# SparkFun_LED_Array_8x7.net
KiCad netlist of a schematic drawn in EAGLE
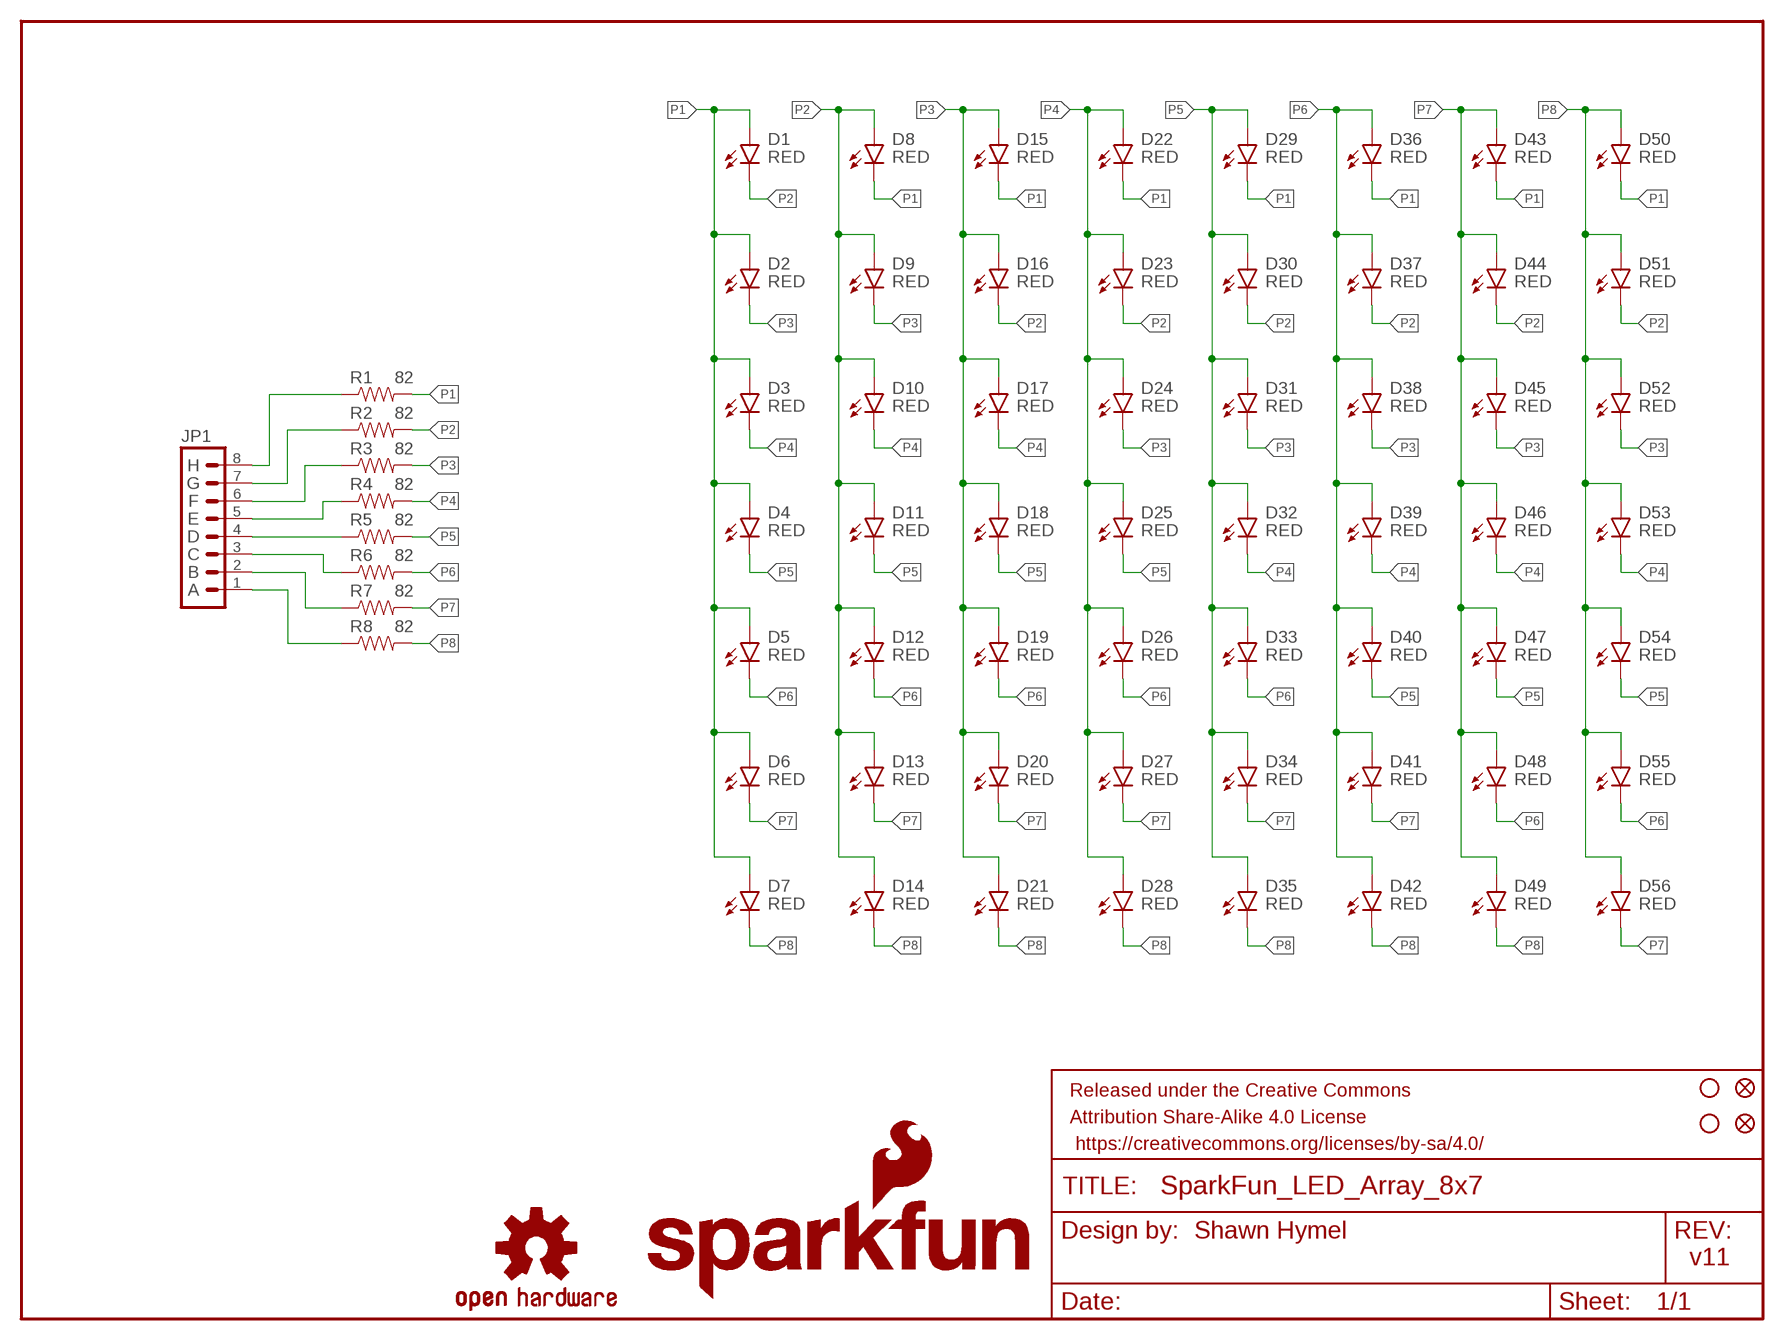
[diagram p0: schematic, sheet 1]

(export (version "E")
  (design (tool "Eeschema 10.0.6"))
  (components
    (comp (ref "D1")
      (value "RED")
      (footprint "eagle-import:LED-0603")
      (libsource (lib "eagle-import") (part "LED-RED0603"))
    )
    (comp (ref "D2")
      (value "RED")
      (footprint "eagle-import:LED-0603")
      (libsource (lib "eagle-import") (part "LED-RED0603"))
    )
    (comp (ref "D3")
      (value "RED")
      (footprint "eagle-import:LED-0603")
      (libsource (lib "eagle-import") (part "LED-RED0603"))
    )
    (comp (ref "D4")
      (value "RED")
      (footprint "eagle-import:LED-0603")
      (libsource (lib "eagle-import") (part "LED-RED0603"))
    )
    (comp (ref "D5")
      (value "RED")
      (footprint "eagle-import:LED-0603")
      (libsource (lib "eagle-import") (part "LED-RED0603"))
    )
    (comp (ref "D6")
      (value "RED")
      (footprint "eagle-import:LED-0603")
      (libsource (lib "eagle-import") (part "LED-RED0603"))
    )
    (comp (ref "D7")
      (value "RED")
      (footprint "eagle-import:LED-0603")
      (libsource (lib "eagle-import") (part "LED-RED0603"))
    )
    (comp (ref "D8")
      (value "RED")
      (footprint "eagle-import:LED-0603")
      (libsource (lib "eagle-import") (part "LED-RED0603"))
    )
    (comp (ref "D9")
      (value "RED")
      (footprint "eagle-import:LED-0603")
      (libsource (lib "eagle-import") (part "LED-RED0603"))
    )
    (comp (ref "D10")
      (value "RED")
      (footprint "eagle-import:LED-0603")
      (libsource (lib "eagle-import") (part "LED-RED0603"))
    )
    (comp (ref "D11")
      (value "RED")
      (footprint "eagle-import:LED-0603")
      (libsource (lib "eagle-import") (part "LED-RED0603"))
    )
    (comp (ref "D12")
      (value "RED")
      (footprint "eagle-import:LED-0603")
      (libsource (lib "eagle-import") (part "LED-RED0603"))
    )
    (comp (ref "D13")
      (value "RED")
      (footprint "eagle-import:LED-0603")
      (libsource (lib "eagle-import") (part "LED-RED0603"))
    )
    (comp (ref "D14")
      (value "RED")
      (footprint "eagle-import:LED-0603")
      (libsource (lib "eagle-import") (part "LED-RED0603"))
    )
    (comp (ref "D15")
      (value "RED")
      (footprint "eagle-import:LED-0603")
      (libsource (lib "eagle-import") (part "LED-RED0603"))
    )
    (comp (ref "D16")
      (value "RED")
      (footprint "eagle-import:LED-0603")
      (libsource (lib "eagle-import") (part "LED-RED0603"))
    )
    (comp (ref "D17")
      (value "RED")
      (footprint "eagle-import:LED-0603")
      (libsource (lib "eagle-import") (part "LED-RED0603"))
    )
    (comp (ref "D18")
      (value "RED")
      (footprint "eagle-import:LED-0603")
      (libsource (lib "eagle-import") (part "LED-RED0603"))
    )
    (comp (ref "D19")
      (value "RED")
      (footprint "eagle-import:LED-0603")
      (libsource (lib "eagle-import") (part "LED-RED0603"))
    )
    (comp (ref "D20")
      (value "RED")
      (footprint "eagle-import:LED-0603")
      (libsource (lib "eagle-import") (part "LED-RED0603"))
    )
    (comp (ref "D21")
      (value "RED")
      (footprint "eagle-import:LED-0603")
      (libsource (lib "eagle-import") (part "LED-RED0603"))
    )
    (comp (ref "D22")
      (value "RED")
      (footprint "eagle-import:LED-0603")
      (libsource (lib "eagle-import") (part "LED-RED0603"))
    )
    (comp (ref "D23")
      (value "RED")
      (footprint "eagle-import:LED-0603")
      (libsource (lib "eagle-import") (part "LED-RED0603"))
    )
    (comp (ref "D24")
      (value "RED")
      (footprint "eagle-import:LED-0603")
      (libsource (lib "eagle-import") (part "LED-RED0603"))
    )
    (comp (ref "D25")
      (value "RED")
      (footprint "eagle-import:LED-0603")
      (libsource (lib "eagle-import") (part "LED-RED0603"))
    )
    (comp (ref "D26")
      (value "RED")
      (footprint "eagle-import:LED-0603")
      (libsource (lib "eagle-import") (part "LED-RED0603"))
    )
    (comp (ref "D27")
      (value "RED")
      (footprint "eagle-import:LED-0603")
      (libsource (lib "eagle-import") (part "LED-RED0603"))
    )
    (comp (ref "D28")
      (value "RED")
      (footprint "eagle-import:LED-0603")
      (libsource (lib "eagle-import") (part "LED-RED0603"))
    )
    (comp (ref "D29")
      (value "RED")
      (footprint "eagle-import:LED-0603")
      (libsource (lib "eagle-import") (part "LED-RED0603"))
    )
    (comp (ref "D30")
      (value "RED")
      (footprint "eagle-import:LED-0603")
      (libsource (lib "eagle-import") (part "LED-RED0603"))
    )
    (comp (ref "D31")
      (value "RED")
      (footprint "eagle-import:LED-0603")
      (libsource (lib "eagle-import") (part "LED-RED0603"))
    )
    (comp (ref "D32")
      (value "RED")
      (footprint "eagle-import:LED-0603")
      (libsource (lib "eagle-import") (part "LED-RED0603"))
    )
    (comp (ref "D33")
      (value "RED")
      (footprint "eagle-import:LED-0603")
      (libsource (lib "eagle-import") (part "LED-RED0603"))
    )
    (comp (ref "D34")
      (value "RED")
      (footprint "eagle-import:LED-0603")
      (libsource (lib "eagle-import") (part "LED-RED0603"))
    )
    (comp (ref "D35")
      (value "RED")
      (footprint "eagle-import:LED-0603")
      (libsource (lib "eagle-import") (part "LED-RED0603"))
    )
    (comp (ref "D36")
      (value "RED")
      (footprint "eagle-import:LED-0603")
      (libsource (lib "eagle-import") (part "LED-RED0603"))
    )
    (comp (ref "D37")
      (value "RED")
      (footprint "eagle-import:LED-0603")
      (libsource (lib "eagle-import") (part "LED-RED0603"))
    )
    (comp (ref "D38")
      (value "RED")
      (footprint "eagle-import:LED-0603")
      (libsource (lib "eagle-import") (part "LED-RED0603"))
    )
    (comp (ref "D39")
      (value "RED")
      (footprint "eagle-import:LED-0603")
      (libsource (lib "eagle-import") (part "LED-RED0603"))
    )
    (comp (ref "D40")
      (value "RED")
      (footprint "eagle-import:LED-0603")
      (libsource (lib "eagle-import") (part "LED-RED0603"))
    )
    (comp (ref "D41")
      (value "RED")
      (footprint "eagle-import:LED-0603")
      (libsource (lib "eagle-import") (part "LED-RED0603"))
    )
    (comp (ref "D42")
      (value "RED")
      (footprint "eagle-import:LED-0603")
      (libsource (lib "eagle-import") (part "LED-RED0603"))
    )
    (comp (ref "D43")
      (value "RED")
      (footprint "eagle-import:LED-0603")
      (libsource (lib "eagle-import") (part "LED-RED0603"))
    )
    (comp (ref "D44")
      (value "RED")
      (footprint "eagle-import:LED-0603")
      (libsource (lib "eagle-import") (part "LED-RED0603"))
    )
    (comp (ref "D45")
      (value "RED")
      (footprint "eagle-import:LED-0603")
      (libsource (lib "eagle-import") (part "LED-RED0603"))
    )
    (comp (ref "D46")
      (value "RED")
      (footprint "eagle-import:LED-0603")
      (libsource (lib "eagle-import") (part "LED-RED0603"))
    )
    (comp (ref "D47")
      (value "RED")
      (footprint "eagle-import:LED-0603")
      (libsource (lib "eagle-import") (part "LED-RED0603"))
    )
    (comp (ref "D48")
      (value "RED")
      (footprint "eagle-import:LED-0603")
      (libsource (lib "eagle-import") (part "LED-RED0603"))
    )
    (comp (ref "D49")
      (value "RED")
      (footprint "eagle-import:LED-0603")
      (libsource (lib "eagle-import") (part "LED-RED0603"))
    )
    (comp (ref "D50")
      (value "RED")
      (footprint "eagle-import:LED-0603")
      (libsource (lib "eagle-import") (part "LED-RED0603"))
    )
    (comp (ref "D51")
      (value "RED")
      (footprint "eagle-import:LED-0603")
      (libsource (lib "eagle-import") (part "LED-RED0603"))
    )
    (comp (ref "D52")
      (value "RED")
      (footprint "eagle-import:LED-0603")
      (libsource (lib "eagle-import") (part "LED-RED0603"))
    )
    (comp (ref "D53")
      (value "RED")
      (footprint "eagle-import:LED-0603")
      (libsource (lib "eagle-import") (part "LED-RED0603"))
    )
    (comp (ref "D54")
      (value "RED")
      (footprint "eagle-import:LED-0603")
      (libsource (lib "eagle-import") (part "LED-RED0603"))
    )
    (comp (ref "D55")
      (value "RED")
      (footprint "eagle-import:LED-0603")
      (libsource (lib "eagle-import") (part "LED-RED0603"))
    )
    (comp (ref "D56")
      (value "RED")
      (footprint "eagle-import:LED-0603")
      (libsource (lib "eagle-import") (part "LED-RED0603"))
    )
    (comp (ref "FID1")
      (value "FIDUCIAL1X2")
      (footprint "eagle-import:FIDUCIAL-1X2")
      (libsource (lib "eagle-import") (part "FIDUCIAL1X2"))
    )
    (comp (ref "FID2")
      (value "FIDUCIAL1X2")
      (footprint "eagle-import:FIDUCIAL-1X2")
      (libsource (lib "eagle-import") (part "FIDUCIAL1X2"))
    )
    (comp (ref "FRAME1")
      (value "FRAME-LETTER")
      (footprint "eagle-import:CREATIVE_COMMONS")
      (libsource (lib "eagle-import") (part "FRAME-LETTER"))
    )
    (comp (ref "JP1")
      (value "M08LOCK_NO_SILK")
      (footprint "eagle-import:1X08_LOCK_NO_SILK")
      (libsource (lib "eagle-import") (part "M08LOCK_NO_SILK"))
    )
    (comp (ref "LOGO2")
      (value "OSHW-LOGOS")
      (footprint "eagle-import:OSHW-LOGO-S")
      (libsource (lib "eagle-import") (part "OSHW-LOGOS"))
    )
    (comp (ref "R1")
      (value "82")
      (footprint "eagle-import:0603-RES")
      (libsource (lib "eagle-import") (part "82OHM-1/10W-1%(0603)SMD"))
    )
    (comp (ref "R2")
      (value "82")
      (footprint "eagle-import:0603-RES")
      (libsource (lib "eagle-import") (part "82OHM-1/10W-1%(0603)SMD"))
    )
    (comp (ref "R3")
      (value "82")
      (footprint "eagle-import:0603-RES")
      (libsource (lib "eagle-import") (part "82OHM-1/10W-1%(0603)SMD"))
    )
    (comp (ref "R4")
      (value "82")
      (footprint "eagle-import:0603-RES")
      (libsource (lib "eagle-import") (part "82OHM-1/10W-1%(0603)SMD"))
    )
    (comp (ref "R5")
      (value "82")
      (footprint "eagle-import:0603-RES")
      (libsource (lib "eagle-import") (part "82OHM-1/10W-1%(0603)SMD"))
    )
    (comp (ref "R6")
      (value "82")
      (footprint "eagle-import:0603-RES")
      (libsource (lib "eagle-import") (part "82OHM-1/10W-1%(0603)SMD"))
    )
    (comp (ref "R7")
      (value "82")
      (footprint "eagle-import:0603-RES")
      (libsource (lib "eagle-import") (part "82OHM-1/10W-1%(0603)SMD"))
    )
    (comp (ref "R8")
      (value "82")
      (footprint "eagle-import:0603-RES")
      (libsource (lib "eagle-import") (part "82OHM-1/10W-1%(0603)SMD"))
    )
    (comp (ref "STANDOFF1")
      (value "STAND-OFF")
      (footprint "eagle-import:STAND-OFF")
      (libsource (lib "eagle-import") (part "STAND-OFF"))
    )
    (comp (ref "STANDOFF2")
      (value "STAND-OFF")
      (footprint "eagle-import:STAND-OFF")
      (libsource (lib "eagle-import") (part "STAND-OFF"))
    )
    (comp (ref "U$1")
      (value "SFE_LOGO_NAME_FLAME.1_INCH")
      (footprint "eagle-import:SFE_LOGO_NAME_FLAME_.1")
      (libsource (lib "eagle-import") (part "SFE_LOGO_NAME_FLAME.1_INCH"))
    )
  )
  (nets
    (net (code "1") (name "Net-(JP1-Pad1)") (class "Default")
      (node (ref "JP1") (pin "1") (pinfunction "1_1") (pintype "passive"))
      (node (ref "R8") (pin "1") (pinfunction "1_1") (pintype "passive"))
    )
    (net (code "2") (name "Net-(JP1-Pad2)") (class "Default")
      (node (ref "JP1") (pin "2") (pinfunction "2_2") (pintype "passive"))
      (node (ref "R7") (pin "1") (pinfunction "1_1") (pintype "passive"))
    )
    (net (code "3") (name "Net-(JP1-Pad3)") (class "Default")
      (node (ref "JP1") (pin "3") (pinfunction "3_3") (pintype "passive"))
      (node (ref "R6") (pin "1") (pinfunction "1_1") (pintype "passive"))
    )
    (net (code "4") (name "Net-(JP1-Pad4)") (class "Default")
      (node (ref "JP1") (pin "4") (pinfunction "4_4") (pintype "passive"))
      (node (ref "R5") (pin "1") (pinfunction "1_1") (pintype "passive"))
    )
    (net (code "5") (name "Net-(JP1-Pad5)") (class "Default")
      (node (ref "JP1") (pin "5") (pinfunction "5_5") (pintype "passive"))
      (node (ref "R4") (pin "1") (pinfunction "1_1") (pintype "passive"))
    )
    (net (code "6") (name "Net-(JP1-Pad6)") (class "Default")
      (node (ref "JP1") (pin "6") (pinfunction "6_6") (pintype "passive"))
      (node (ref "R3") (pin "1") (pinfunction "1_1") (pintype "passive"))
    )
    (net (code "7") (name "Net-(JP1-Pad7)") (class "Default")
      (node (ref "JP1") (pin "7") (pinfunction "7_7") (pintype "passive"))
      (node (ref "R2") (pin "1") (pinfunction "1_1") (pintype "passive"))
    )
    (net (code "8") (name "Net-(JP1-Pad8)") (class "Default")
      (node (ref "JP1") (pin "8") (pinfunction "8_8") (pintype "passive"))
      (node (ref "R1") (pin "1") (pinfunction "1_1") (pintype "passive"))
    )
    (net (code "9") (name "P1") (class "Default")
      (node (ref "D1") (pin "A") (pinfunction "A_A") (pintype "passive"))
      (node (ref "D15") (pin "C") (pinfunction "C_C") (pintype "passive"))
      (node (ref "D2") (pin "A") (pinfunction "A_A") (pintype "passive"))
      (node (ref "D22") (pin "C") (pinfunction "C_C") (pintype "passive"))
      (node (ref "D29") (pin "C") (pinfunction "C_C") (pintype "passive"))
      (node (ref "D3") (pin "A") (pinfunction "A_A") (pintype "passive"))
      (node (ref "D36") (pin "C") (pinfunction "C_C") (pintype "passive"))
      (node (ref "D4") (pin "A") (pinfunction "A_A") (pintype "passive"))
      (node (ref "D43") (pin "C") (pinfunction "C_C") (pintype "passive"))
      (node (ref "D5") (pin "A") (pinfunction "A_A") (pintype "passive"))
      (node (ref "D50") (pin "C") (pinfunction "C_C") (pintype "passive"))
      (node (ref "D6") (pin "A") (pinfunction "A_A") (pintype "passive"))
      (node (ref "D7") (pin "A") (pinfunction "A_A") (pintype "passive"))
      (node (ref "D8") (pin "C") (pinfunction "C_C") (pintype "passive"))
      (node (ref "R1") (pin "2") (pinfunction "2_2") (pintype "passive"))
    )
    (net (code "10") (name "P2") (class "Default")
      (node (ref "D1") (pin "C") (pinfunction "C_C") (pintype "passive"))
      (node (ref "D10") (pin "A") (pinfunction "A_A") (pintype "passive"))
      (node (ref "D11") (pin "A") (pinfunction "A_A") (pintype "passive"))
      (node (ref "D12") (pin "A") (pinfunction "A_A") (pintype "passive"))
      (node (ref "D13") (pin "A") (pinfunction "A_A") (pintype "passive"))
      (node (ref "D14") (pin "A") (pinfunction "A_A") (pintype "passive"))
      (node (ref "D16") (pin "C") (pinfunction "C_C") (pintype "passive"))
      (node (ref "D23") (pin "C") (pinfunction "C_C") (pintype "passive"))
      (node (ref "D30") (pin "C") (pinfunction "C_C") (pintype "passive"))
      (node (ref "D37") (pin "C") (pinfunction "C_C") (pintype "passive"))
      (node (ref "D44") (pin "C") (pinfunction "C_C") (pintype "passive"))
      (node (ref "D51") (pin "C") (pinfunction "C_C") (pintype "passive"))
      (node (ref "D8") (pin "A") (pinfunction "A_A") (pintype "passive"))
      (node (ref "D9") (pin "A") (pinfunction "A_A") (pintype "passive"))
      (node (ref "R2") (pin "2") (pinfunction "2_2") (pintype "passive"))
    )
    (net (code "11") (name "P3") (class "Default")
      (node (ref "D15") (pin "A") (pinfunction "A_A") (pintype "passive"))
      (node (ref "D16") (pin "A") (pinfunction "A_A") (pintype "passive"))
      (node (ref "D17") (pin "A") (pinfunction "A_A") (pintype "passive"))
      (node (ref "D18") (pin "A") (pinfunction "A_A") (pintype "passive"))
      (node (ref "D19") (pin "A") (pinfunction "A_A") (pintype "passive"))
      (node (ref "D2") (pin "C") (pinfunction "C_C") (pintype "passive"))
      (node (ref "D20") (pin "A") (pinfunction "A_A") (pintype "passive"))
      (node (ref "D21") (pin "A") (pinfunction "A_A") (pintype "passive"))
      (node (ref "D24") (pin "C") (pinfunction "C_C") (pintype "passive"))
      (node (ref "D31") (pin "C") (pinfunction "C_C") (pintype "passive"))
      (node (ref "D38") (pin "C") (pinfunction "C_C") (pintype "passive"))
      (node (ref "D45") (pin "C") (pinfunction "C_C") (pintype "passive"))
      (node (ref "D52") (pin "C") (pinfunction "C_C") (pintype "passive"))
      (node (ref "D9") (pin "C") (pinfunction "C_C") (pintype "passive"))
      (node (ref "R3") (pin "2") (pinfunction "2_2") (pintype "passive"))
    )
    (net (code "12") (name "P4") (class "Default")
      (node (ref "D10") (pin "C") (pinfunction "C_C") (pintype "passive"))
      (node (ref "D17") (pin "C") (pinfunction "C_C") (pintype "passive"))
      (node (ref "D22") (pin "A") (pinfunction "A_A") (pintype "passive"))
      (node (ref "D23") (pin "A") (pinfunction "A_A") (pintype "passive"))
      (node (ref "D24") (pin "A") (pinfunction "A_A") (pintype "passive"))
      (node (ref "D25") (pin "A") (pinfunction "A_A") (pintype "passive"))
      (node (ref "D26") (pin "A") (pinfunction "A_A") (pintype "passive"))
      (node (ref "D27") (pin "A") (pinfunction "A_A") (pintype "passive"))
      (node (ref "D28") (pin "A") (pinfunction "A_A") (pintype "passive"))
      (node (ref "D3") (pin "C") (pinfunction "C_C") (pintype "passive"))
      (node (ref "D32") (pin "C") (pinfunction "C_C") (pintype "passive"))
      (node (ref "D39") (pin "C") (pinfunction "C_C") (pintype "passive"))
      (node (ref "D46") (pin "C") (pinfunction "C_C") (pintype "passive"))
      (node (ref "D53") (pin "C") (pinfunction "C_C") (pintype "passive"))
      (node (ref "R4") (pin "2") (pinfunction "2_2") (pintype "passive"))
    )
    (net (code "13") (name "P5") (class "Default")
      (node (ref "D11") (pin "C") (pinfunction "C_C") (pintype "passive"))
      (node (ref "D18") (pin "C") (pinfunction "C_C") (pintype "passive"))
      (node (ref "D25") (pin "C") (pinfunction "C_C") (pintype "passive"))
      (node (ref "D29") (pin "A") (pinfunction "A_A") (pintype "passive"))
      (node (ref "D30") (pin "A") (pinfunction "A_A") (pintype "passive"))
      (node (ref "D31") (pin "A") (pinfunction "A_A") (pintype "passive"))
      (node (ref "D32") (pin "A") (pinfunction "A_A") (pintype "passive"))
      (node (ref "D33") (pin "A") (pinfunction "A_A") (pintype "passive"))
      (node (ref "D34") (pin "A") (pinfunction "A_A") (pintype "passive"))
      (node (ref "D35") (pin "A") (pinfunction "A_A") (pintype "passive"))
      (node (ref "D4") (pin "C") (pinfunction "C_C") (pintype "passive"))
      (node (ref "D40") (pin "C") (pinfunction "C_C") (pintype "passive"))
      (node (ref "D47") (pin "C") (pinfunction "C_C") (pintype "passive"))
      (node (ref "D54") (pin "C") (pinfunction "C_C") (pintype "passive"))
      (node (ref "R5") (pin "2") (pinfunction "2_2") (pintype "passive"))
    )
    (net (code "14") (name "P6") (class "Default")
      (node (ref "D12") (pin "C") (pinfunction "C_C") (pintype "passive"))
      (node (ref "D19") (pin "C") (pinfunction "C_C") (pintype "passive"))
      (node (ref "D26") (pin "C") (pinfunction "C_C") (pintype "passive"))
      (node (ref "D33") (pin "C") (pinfunction "C_C") (pintype "passive"))
      (node (ref "D36") (pin "A") (pinfunction "A_A") (pintype "passive"))
      (node (ref "D37") (pin "A") (pinfunction "A_A") (pintype "passive"))
      (node (ref "D38") (pin "A") (pinfunction "A_A") (pintype "passive"))
      (node (ref "D39") (pin "A") (pinfunction "A_A") (pintype "passive"))
      (node (ref "D40") (pin "A") (pinfunction "A_A") (pintype "passive"))
      (node (ref "D41") (pin "A") (pinfunction "A_A") (pintype "passive"))
      (node (ref "D42") (pin "A") (pinfunction "A_A") (pintype "passive"))
      (node (ref "D48") (pin "C") (pinfunction "C_C") (pintype "passive"))
      (node (ref "D5") (pin "C") (pinfunction "C_C") (pintype "passive"))
      (node (ref "D55") (pin "C") (pinfunction "C_C") (pintype "passive"))
      (node (ref "R6") (pin "2") (pinfunction "2_2") (pintype "passive"))
    )
    (net (code "15") (name "P7") (class "Default")
      (node (ref "D13") (pin "C") (pinfunction "C_C") (pintype "passive"))
      (node (ref "D20") (pin "C") (pinfunction "C_C") (pintype "passive"))
      (node (ref "D27") (pin "C") (pinfunction "C_C") (pintype "passive"))
      (node (ref "D34") (pin "C") (pinfunction "C_C") (pintype "passive"))
      (node (ref "D41") (pin "C") (pinfunction "C_C") (pintype "passive"))
      (node (ref "D43") (pin "A") (pinfunction "A_A") (pintype "passive"))
      (node (ref "D44") (pin "A") (pinfunction "A_A") (pintype "passive"))
      (node (ref "D45") (pin "A") (pinfunction "A_A") (pintype "passive"))
      (node (ref "D46") (pin "A") (pinfunction "A_A") (pintype "passive"))
      (node (ref "D47") (pin "A") (pinfunction "A_A") (pintype "passive"))
      (node (ref "D48") (pin "A") (pinfunction "A_A") (pintype "passive"))
      (node (ref "D49") (pin "A") (pinfunction "A_A") (pintype "passive"))
      (node (ref "D56") (pin "C") (pinfunction "C_C") (pintype "passive"))
      (node (ref "D6") (pin "C") (pinfunction "C_C") (pintype "passive"))
      (node (ref "R7") (pin "2") (pinfunction "2_2") (pintype "passive"))
    )
    (net (code "16") (name "P8") (class "Default")
      (node (ref "D14") (pin "C") (pinfunction "C_C") (pintype "passive"))
      (node (ref "D21") (pin "C") (pinfunction "C_C") (pintype "passive"))
      (node (ref "D28") (pin "C") (pinfunction "C_C") (pintype "passive"))
      (node (ref "D35") (pin "C") (pinfunction "C_C") (pintype "passive"))
      (node (ref "D42") (pin "C") (pinfunction "C_C") (pintype "passive"))
      (node (ref "D49") (pin "C") (pinfunction "C_C") (pintype "passive"))
      (node (ref "D50") (pin "A") (pinfunction "A_A") (pintype "passive"))
      (node (ref "D51") (pin "A") (pinfunction "A_A") (pintype "passive"))
      (node (ref "D52") (pin "A") (pinfunction "A_A") (pintype "passive"))
      (node (ref "D53") (pin "A") (pinfunction "A_A") (pintype "passive"))
      (node (ref "D54") (pin "A") (pinfunction "A_A") (pintype "passive"))
      (node (ref "D55") (pin "A") (pinfunction "A_A") (pintype "passive"))
      (node (ref "D56") (pin "A") (pinfunction "A_A") (pintype "passive"))
      (node (ref "D7") (pin "C") (pinfunction "C_C") (pintype "passive"))
      (node (ref "R8") (pin "2") (pinfunction "2_2") (pintype "passive"))
    )
  )
)
